# 04_-_USB.net
KiCad netlist of a schematic drawn in Altium Designer
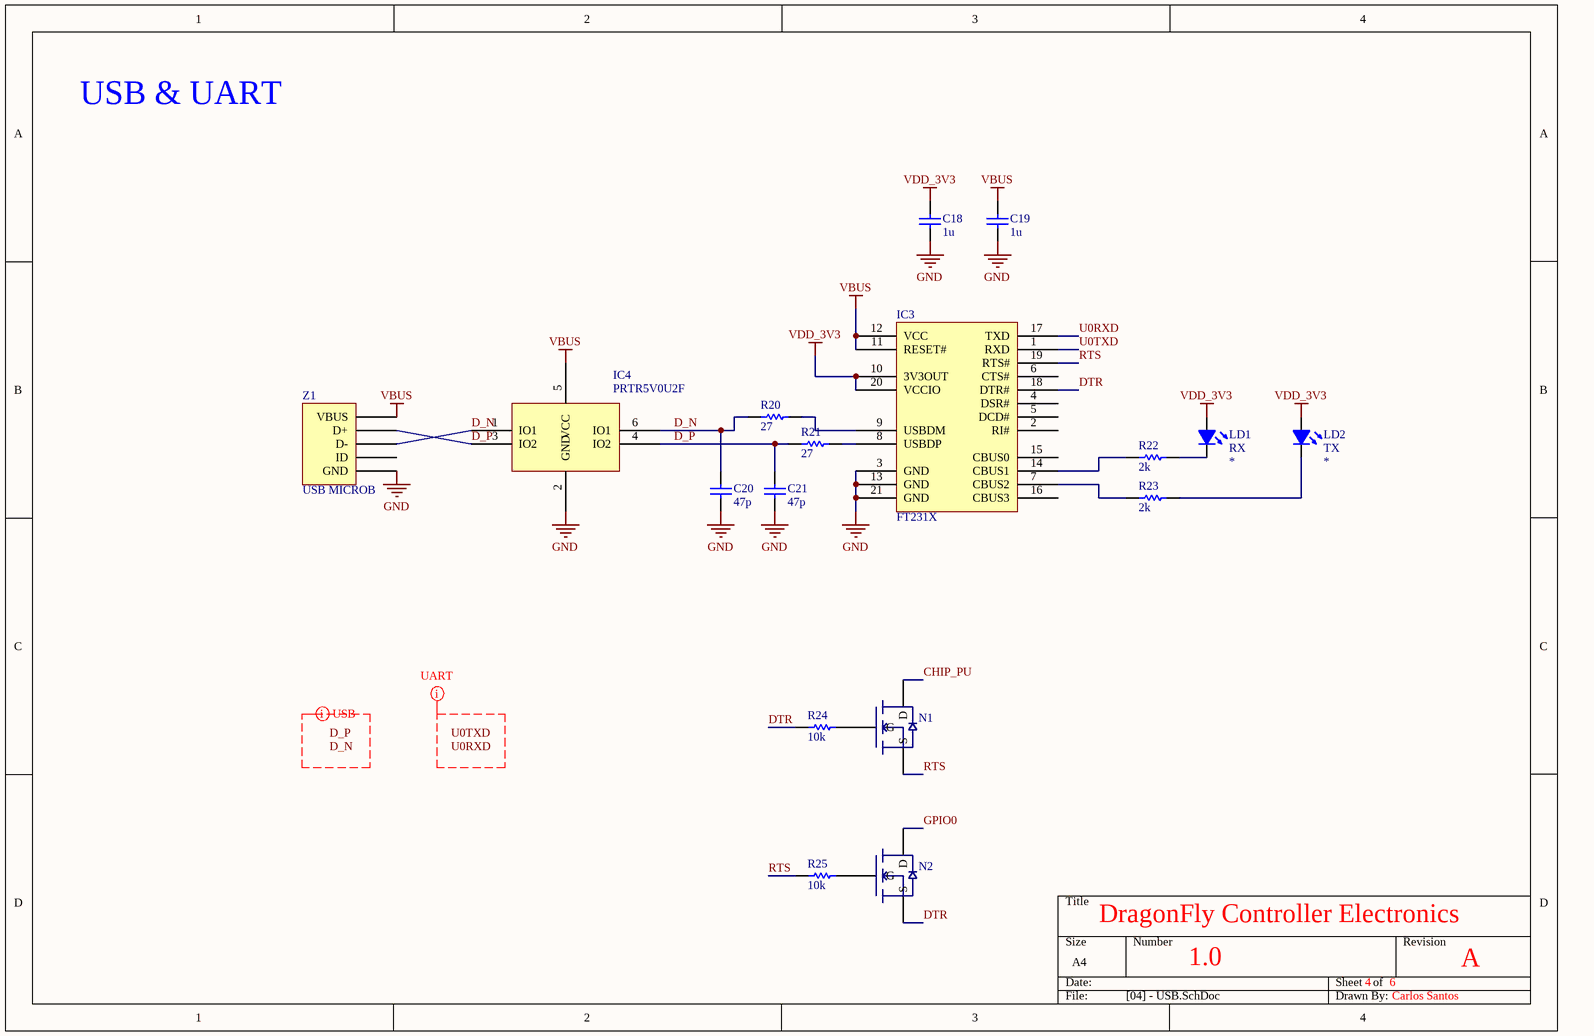
[diagram p0: [04] - USB.SchDoc]

(export (version "E")
  (design (tool "Eeschema 10.0.6"))
  (components
    (comp (ref "C18")
      (value "1u")
      (footprint "0402 - Capacitor")
      (fields (field (name "Comment") "Capacitor"))
      (libsource (lib "Mine") (part "Capacitor"))
    )
    (comp (ref "C19")
      (value "1u")
      (footprint "0402 - Capacitor")
      (fields (field (name "Comment") "Capacitor"))
      (libsource (lib "Mine") (part "Capacitor"))
    )
    (comp (ref "C20")
      (value "47p")
      (footprint "0402 - Capacitor")
      (fields (field (name "Comment") "Capacitor"))
      (libsource (lib "Mine") (part "Capacitor"))
    )
    (comp (ref "C21")
      (value "47p")
      (footprint "0402 - Capacitor")
      (fields (field (name "Comment") "Capacitor"))
      (libsource (lib "Mine") (part "Capacitor"))
    )
    (comp (ref "IC3")
      (value "FT231X")
      (footprint "QFN20-127P600-8N")
      (fields (field (name "DIGIKEY PART #") "768-1128-1-ND"))
      (libsource (lib "Mine") (part "FT231X"))
    )
    (comp (ref "IC4")
      (value "PRTR5V0U2F")
      (footprint "SOT886")
      (fields (field (name "DIGIKEY PART #") "1727-4161-6-ND"))
      (libsource (lib "Mine") (part "PRTR5V0U2F"))
    )
    (comp (ref "LD1")
      (value "Led")
      (footprint "0402 - Led")
      (fields (field (name "COLOR") "RX") (field (name "VF") "*"))
      (libsource (lib "Mine") (part "Led"))
    )
    (comp (ref "LD2")
      (value "Led")
      (footprint "0402 - Led")
      (fields (field (name "COLOR") "TX") (field (name "VF") "*"))
      (libsource (lib "Mine") (part "Led"))
    )
    (comp (ref "N1") (value "N-MOSFET") (footprint "DFN1006-3") (libsource (lib "Mine") (part "N-MOSFET")))
    (comp (ref "N2") (value "N-MOSFET") (footprint "DFN1006-3") (libsource (lib "Mine") (part "N-MOSFET")))
    (comp (ref "R20")
      (value "27")
      (footprint "0402 - Resistor")
      (fields (field (name "Comment") "Resistor"))
      (libsource (lib "Mine") (part "Resistor"))
    )
    (comp (ref "R21")
      (value "27")
      (footprint "0402 - Resistor")
      (fields (field (name "Comment") "Resistor"))
      (libsource (lib "Mine") (part "Resistor"))
    )
    (comp (ref "R22")
      (value "2k")
      (footprint "0402 - Resistor")
      (fields (field (name "Comment") "Resistor"))
      (libsource (lib "Mine") (part "Resistor"))
    )
    (comp (ref "R23")
      (value "2k")
      (footprint "0402 - Resistor")
      (fields (field (name "Comment") "Resistor"))
      (libsource (lib "Mine") (part "Resistor"))
    )
    (comp (ref "R24")
      (value "10k")
      (footprint "0402 - Resistor")
      (fields (field (name "Comment") "Resistor"))
      (libsource (lib "Mine") (part "Resistor"))
    )
    (comp (ref "R25")
      (value "10k")
      (footprint "0402 - Resistor")
      (fields (field (name "Comment") "Resistor"))
      (libsource (lib "Mine") (part "Resistor"))
    )
    (comp (ref "Z1")
      (value "USB MICROB")
      (footprint "USB - microB")
      (description "609-4613-1-ND")
      (libsource (lib "Mine") (part "USB - microB"))
    )
  )
  (nets
    (net (code "1") (name "/CHIP_PU") (class "Default")
      (node (ref "N1") (pin "3") (pinfunction "D_3") (pintype "passive"))
    )
    (net (code "2") (name "/DTR") (class "Default")
      (node (ref "IC3") (pin "18") (pinfunction "DTR#_18") (pintype "passive"))
      (node (ref "N2") (pin "1") (pinfunction "S_1") (pintype "passive"))
      (node (ref "R24") (pin "1") (pinfunction "1_1") (pintype "passive"))
    )
    (net (code "3") (name "/D_N") (class "Default")
      (node (ref "C20") (pin "2") (pinfunction "2_2") (pintype "passive"))
      (node (ref "IC4") (pin "1") (pinfunction "IO1_1") (pintype "passive"))
      (node (ref "IC4") (pin "6") (pinfunction "IO1_6") (pintype "passive"))
      (node (ref "R20") (pin "1") (pinfunction "1_1") (pintype "passive"))
      (node (ref "Z1") (pin "2") (pinfunction "D-_2") (pintype "passive"))
    )
    (net (code "4") (name "/D_P") (class "Default")
      (node (ref "C21") (pin "2") (pinfunction "2_2") (pintype "passive"))
      (node (ref "IC4") (pin "3") (pinfunction "IO2_3") (pintype "passive"))
      (node (ref "IC4") (pin "4") (pinfunction "IO2_4") (pintype "passive"))
      (node (ref "R21") (pin "1") (pinfunction "1_1") (pintype "passive"))
      (node (ref "Z1") (pin "3") (pinfunction "D+_3") (pintype "passive"))
    )
    (net (code "5") (name "/GPIO0") (class "Default")
      (node (ref "N2") (pin "3") (pinfunction "D_3") (pintype "passive"))
    )
    (net (code "6") (name "/RTS") (class "Default")
      (node (ref "IC3") (pin "19") (pinfunction "RTS#_19") (pintype "passive"))
      (node (ref "N1") (pin "1") (pinfunction "S_1") (pintype "passive"))
      (node (ref "R25") (pin "1") (pinfunction "1_1") (pintype "passive"))
    )
    (net (code "7") (name "/U0RXD") (class "Default")
      (node (ref "IC3") (pin "17") (pinfunction "TXD_17") (pintype "passive"))
    )
    (net (code "8") (name "/U0TXD") (class "Default")
      (node (ref "IC3") (pin "1") (pinfunction "RXD_1") (pintype "passive"))
    )
    (net (code "9") (name "GND") (class "Default")
      (node (ref "C18") (pin "1") (pinfunction "1_1") (pintype "passive"))
      (node (ref "C19") (pin "1") (pinfunction "1_1") (pintype "passive"))
      (node (ref "C20") (pin "1") (pinfunction "1_1") (pintype "passive"))
      (node (ref "C21") (pin "1") (pinfunction "1_1") (pintype "passive"))
      (node (ref "IC3") (pin "13") (pinfunction "GND_13") (pintype "passive"))
      (node (ref "IC3") (pin "21") (pinfunction "GND_21") (pintype "passive"))
      (node (ref "IC3") (pin "3") (pinfunction "GND_3") (pintype "passive"))
      (node (ref "IC4") (pin "2") (pinfunction "GND_2") (pintype "passive"))
      (node (ref "Z1") (pin "5") (pinfunction "GND_5") (pintype "passive"))
    )
    (net (code "10") (name "Net-(IC3-CBUS1)") (class "Default")
      (node (ref "IC3") (pin "14") (pinfunction "CBUS1_14") (pintype "passive"))
      (node (ref "R22") (pin "1") (pinfunction "1_1") (pintype "passive"))
    )
    (net (code "11") (name "Net-(IC3-CBUS2)") (class "Default")
      (node (ref "IC3") (pin "7") (pinfunction "CBUS2_7") (pintype "passive"))
      (node (ref "R23") (pin "1") (pinfunction "1_1") (pintype "passive"))
    )
    (net (code "12") (name "Net-(IC3-USBDM)") (class "Default")
      (node (ref "IC3") (pin "9") (pinfunction "USBDM_9") (pintype "passive"))
      (node (ref "R20") (pin "2") (pinfunction "2_2") (pintype "passive"))
    )
    (net (code "13") (name "Net-(IC3-USBDP)") (class "Default")
      (node (ref "IC3") (pin "8") (pinfunction "USBDP_8") (pintype "passive"))
      (node (ref "R21") (pin "2") (pinfunction "2_2") (pintype "passive"))
    )
    (net (code "14") (name "Net-(LD1-K)") (class "Default")
      (node (ref "LD1") (pin "2") (pinfunction "K_2") (pintype "passive"))
      (node (ref "R22") (pin "2") (pinfunction "2_2") (pintype "passive"))
    )
    (net (code "15") (name "Net-(LD2-K)") (class "Default")
      (node (ref "LD2") (pin "2") (pinfunction "K_2") (pintype "passive"))
      (node (ref "R23") (pin "2") (pinfunction "2_2") (pintype "passive"))
    )
    (net (code "16") (name "Net-(N1-G)") (class "Default")
      (node (ref "N1") (pin "2") (pinfunction "G_2") (pintype "passive"))
      (node (ref "R24") (pin "2") (pinfunction "2_2") (pintype "passive"))
    )
    (net (code "17") (name "Net-(N2-G)") (class "Default")
      (node (ref "N2") (pin "2") (pinfunction "G_2") (pintype "passive"))
      (node (ref "R25") (pin "2") (pinfunction "2_2") (pintype "passive"))
    )
    (net (code "18") (name "VBUS") (class "Default")
      (node (ref "C19") (pin "2") (pinfunction "2_2") (pintype "passive"))
      (node (ref "IC3") (pin "11") (pinfunction "RESET#_11") (pintype "passive"))
      (node (ref "IC3") (pin "12") (pinfunction "VCC_12") (pintype "passive"))
      (node (ref "IC4") (pin "5") (pinfunction "VCC_5") (pintype "passive"))
      (node (ref "Z1") (pin "1") (pinfunction "VBUS_1") (pintype "passive"))
    )
    (net (code "19") (name "VDD_3V3") (class "Default")
      (node (ref "C18") (pin "2") (pinfunction "2_2") (pintype "passive"))
      (node (ref "IC3") (pin "10") (pinfunction "3V3OUT_10") (pintype "passive"))
      (node (ref "IC3") (pin "20") (pinfunction "VCCIO_20") (pintype "passive"))
      (node (ref "LD1") (pin "1") (pinfunction "A_1") (pintype "passive"))
      (node (ref "LD2") (pin "1") (pinfunction "A_1") (pintype "passive"))
    )
    (net (code "20") (name "unconnected-(IC3-CBUS0-Pad15)") (class "Default")
      (node (ref "IC3") (pin "15") (pinfunction "CBUS0_15") (pintype "passive"))
    )
    (net (code "21") (name "unconnected-(IC3-CBUS3-Pad16)") (class "Default")
      (node (ref "IC3") (pin "16") (pinfunction "CBUS3_16") (pintype "passive"))
    )
    (net (code "22") (name "unconnected-(IC3-CTS#-Pad6)") (class "Default")
      (node (ref "IC3") (pin "6") (pinfunction "CTS#_6") (pintype "passive"))
    )
    (net (code "23") (name "unconnected-(IC3-DCD#-Pad5)") (class "Default")
      (node (ref "IC3") (pin "5") (pinfunction "DCD#_5") (pintype "passive"))
    )
    (net (code "24") (name "unconnected-(IC3-DSR#-Pad4)") (class "Default")
      (node (ref "IC3") (pin "4") (pinfunction "DSR#_4") (pintype "passive"))
    )
    (net (code "25") (name "unconnected-(IC3-RI#-Pad2)") (class "Default")
      (node (ref "IC3") (pin "2") (pinfunction "RI#_2") (pintype "passive"))
    )
    (net (code "26") (name "unconnected-(Z1-ID-Pad4)") (class "Default")
      (node (ref "Z1") (pin "4") (pinfunction "ID_4") (pintype "passive"))
    )
  )
)
